# Top.net
KiCad netlist of a schematic drawn in Altium Designer
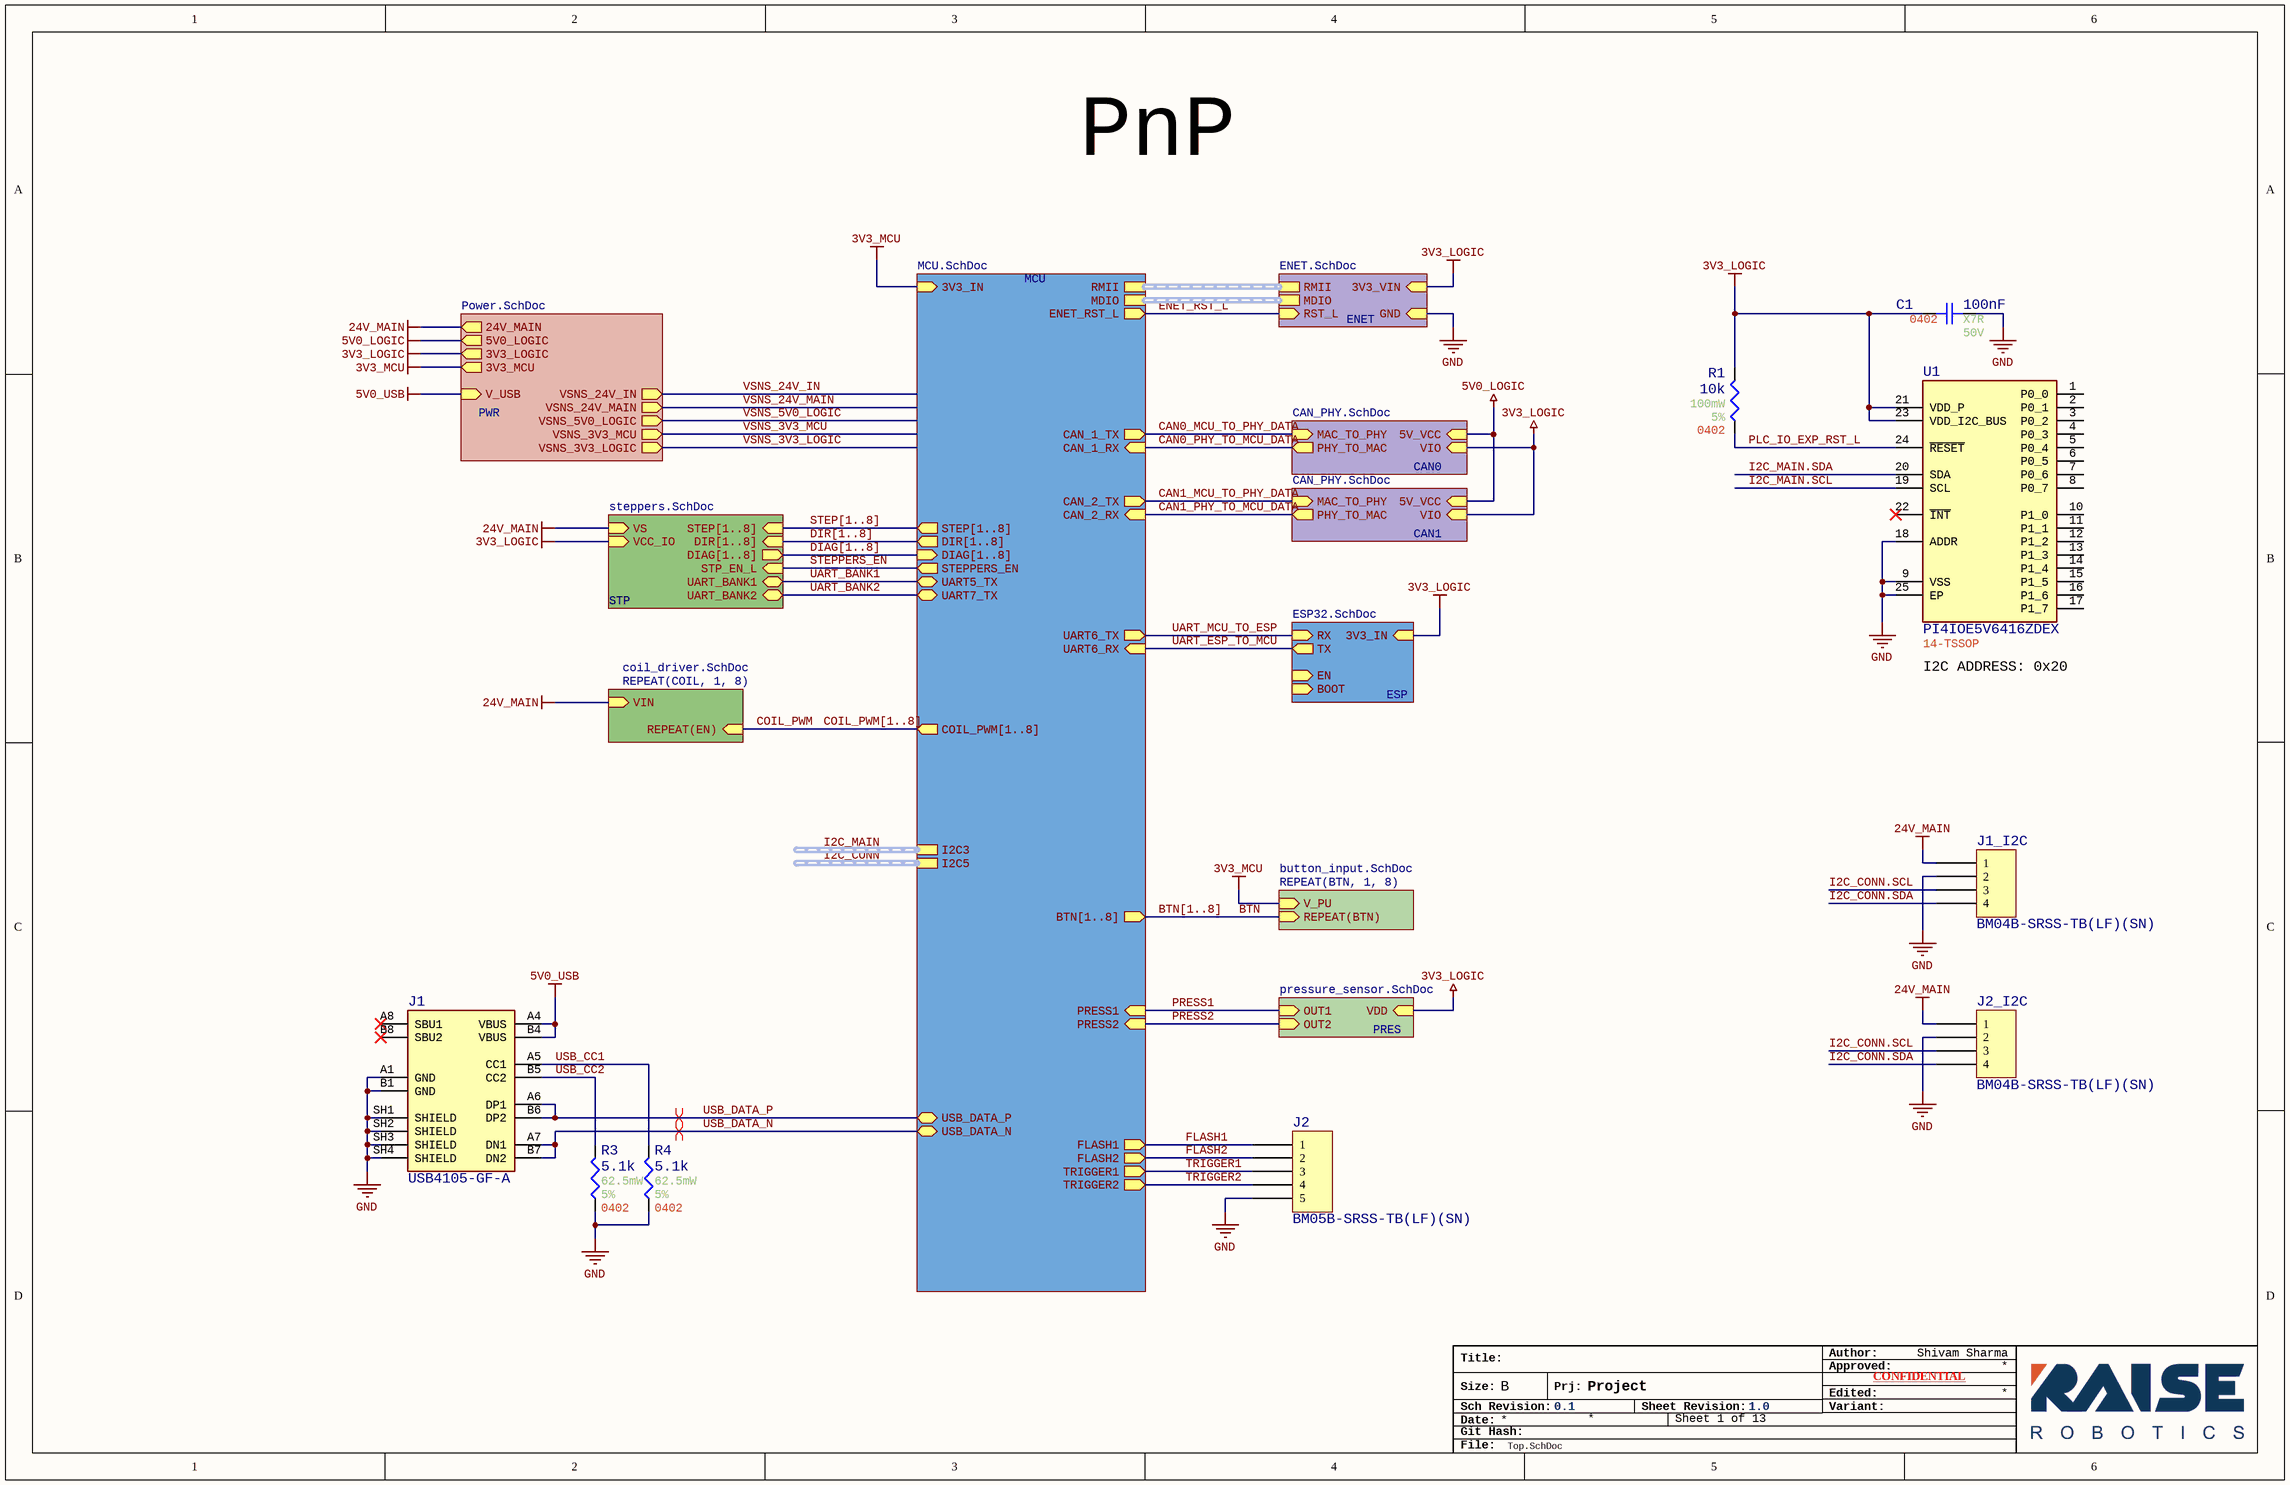
[diagram p0: Top.SchDoc]

(export (version "E")
  (design (tool "Eeschema 10.0.6"))
  (components
    (comp (ref "C1")
      (value "100nF")
      (footprint "Generic 0402 capacitor")
      (fields
        (field (name "TEMPERATURE COEFFICIENT") "X7R")
        (field (name "VOLTAGE RATING") "50V")
        (field (name "CASE/PACKAGE") "0402")
        (field (name "TOLERANCE") "10%")
        (field (name "Comment") "GRT155R71H104KE01D")
      )
      (libsource (lib "Raise Robotics") (part "Unpolarized Capacitor"))
    )
    (comp (ref "J1")
      (value "USB4105-GF-A")
      (footprint "USB-C_USB4105-GF-A")
      (description "USB Connector, 24 Contact(s), Female, Right Angle, Solder Terminal, Locking, Receptacle")
      (fields (field (name "MANUFACTURER") "Molex"))
      (libsource (lib "Raise Robotics") (part "USB4105-GF-A"))
    )
    (comp (ref "J1_I2C")
      (value "BM04B-SRSS-TB(LF)(SN)")
      (footprint "JST BM04B-SRSS-TB")
      (description "CONN HEADER SMD 4POS 1MM")
      (fields (field (name "MANUFACTURER") "JST Sales America Inc."))
      (libsource (lib "Celestial Altium Library - altium_library") (part "4 Pin"))
    )
    (comp (ref "J2")
      (value "BM05B-SRSS-TB(LF)(SN)")
      (footprint "JST BM05B-SRSS-TB")
      (description "CONN HEADER SMD 5POS 1MM")
      (fields (field (name "MANUFACTURER") "JST Sales America Inc."))
      (libsource (lib "Celestial Altium Library - altium_library") (part "5 Pin"))
    )
    (comp (ref "J2_I2C")
      (value "BM04B-SRSS-TB(LF)(SN)")
      (footprint "JST BM04B-SRSS-TB")
      (description "CONN HEADER SMD 4POS 1MM")
      (fields (field (name "MANUFACTURER") "JST Sales America Inc."))
      (libsource (lib "Celestial Altium Library - altium_library") (part "4 Pin"))
    )
    (comp (ref "R1")
      (value "10k")
      (footprint "Generic 0402 Resistor")
      (description "Res Thick Film 0402 10K Ohm 5% 1/10W ±200ppm/°C Molded SMD Punched Carrier T/R")
      (fields
        (field (name "POWER") "100mW")
        (field (name "TOLERANCE") "5%")
        (field (name "CASE/PACKAGE") "0402")
        (field (name "Comment") "ERJ-2GEJ103X")
      )
      (libsource (lib "Raise Robotics") (part "Resistor"))
    )
    (comp (ref "R3")
      (value "5.1k")
      (footprint "Generic 0402 Resistor")
      (description "Res Thick Film 0402 5.1K Ohm 5% 0.063W ±100ppm/°C Molded SMD Paper T/R")
      (fields
        (field (name "POWER") "62.5mW")
        (field (name "TOLERANCE") "5%")
        (field (name "CASE/PACKAGE") "0402")
        (field (name "Comment") "RMCF0402JT5K10")
      )
      (libsource (lib "Raise Robotics") (part "Resistor"))
    )
    (comp (ref "R4")
      (value "5.1k")
      (footprint "Generic 0402 Resistor")
      (description "Res Thick Film 0402 5.1K Ohm 5% 0.063W ±100ppm/°C Molded SMD Paper T/R")
      (fields
        (field (name "POWER") "62.5mW")
        (field (name "TOLERANCE") "5%")
        (field (name "CASE/PACKAGE") "0402")
        (field (name "Comment") "RMCF0402JT5K10")
      )
      (libsource (lib "Raise Robotics") (part "Resistor"))
    )
    (comp (ref "U1")
      (value "PI4IOE5V6416ZDEX")
      (footprint "PI4IOE5V6416ZDEX")
      (description "16-bit I2C General Purpose IO Expander with Interrupt, Reset, -40 to 85 °C, RoHS")
      (fields (field (name "CASE/PACKAGE") "14-TSSOP"))
      (libsource (lib "Raise Robotics") (part "PI4IOE5V6416ZDEX"))
    )
  )
  (nets
    (net (code "56") (name "/FLASH1") (class "Default")
      (node (ref "J2") (pin "1") (pinfunction "1_1") (pintype "passive"))
    )
    (net (code "57") (name "/FLASH2") (class "Default")
      (node (ref "J2") (pin "2") (pinfunction "2_2") (pintype "passive"))
    )
    (net (code "58") (name "/I2C_CONN.SCL") (class "Default")
      (node (ref "J1_I2C") (pin "3") (pinfunction "3_3") (pintype "passive"))
      (node (ref "J2_I2C") (pin "3") (pinfunction "3_3") (pintype "passive"))
    )
    (net (code "59") (name "/I2C_CONN.SDA") (class "Default")
      (node (ref "J1_I2C") (pin "4") (pinfunction "4_4") (pintype "passive"))
      (node (ref "J2_I2C") (pin "4") (pinfunction "4_4") (pintype "passive"))
    )
    (net (code "60") (name "/I2C_MAIN.SCL") (class "Default")
      (node (ref "U1") (pin "19") (pinfunction "SCL_19") (pintype "passive"))
    )
    (net (code "61") (name "/I2C_MAIN.SDA") (class "Default")
      (node (ref "U1") (pin "20") (pinfunction "SDA_20") (pintype "passive"))
    )
    (net (code "63") (name "/PLC_IO_EXP_RST_L") (class "Default")
      (node (ref "R1") (pin "1") (pinfunction "1_1") (pintype "passive"))
      (node (ref "U1") (pin "24") (pinfunction "~{RESET}_24") (pintype "passive"))
    )
    (net (code "69") (name "/TRIGGER1") (class "Default")
      (node (ref "J2") (pin "3") (pinfunction "3_3") (pintype "passive"))
    )
    (net (code "70") (name "/TRIGGER2") (class "Default")
      (node (ref "J2") (pin "4") (pinfunction "4_4") (pintype "passive"))
    )
    (net (code "75") (name "/USB_CC1") (class "Default")
      (node (ref "J1") (pin "A5") (pinfunction "CC1_A5") (pintype "passive"))
      (node (ref "R4") (pin "2") (pinfunction "2_2") (pintype "passive"))
    )
    (net (code "76") (name "/USB_CC2") (class "Default")
      (node (ref "J1") (pin "B5") (pinfunction "CC2_B5") (pintype "passive"))
      (node (ref "R3") (pin "2") (pinfunction "2_2") (pintype "passive"))
    )
    (net (code "77") (name "/USB_DATA_N") (class "Default")
      (node (ref "J1") (pin "A7") (pinfunction "DN1_A7") (pintype "passive"))
      (node (ref "J1") (pin "B7") (pinfunction "DN2_B7") (pintype "passive"))
    )
    (net (code "78") (name "/USB_DATA_P") (class "Default")
      (node (ref "J1") (pin "A6") (pinfunction "DP1_A6") (pintype "passive"))
      (node (ref "J1") (pin "B6") (pinfunction "DP2_B6") (pintype "passive"))
    )
    (net (code "86") (name "3V3_LOGIC") (class "Default")
      (node (ref "C1") (pin "2") (pinfunction "2_2") (pintype "passive"))
      (node (ref "R1") (pin "2") (pinfunction "2_2") (pintype "passive"))
      (node (ref "U1") (pin "21") (pinfunction "VDD_P_21") (pintype "passive"))
      (node (ref "U1") (pin "23") (pinfunction "VDD_I2C_BUS_23") (pintype "passive"))
    )
    (net (code "89") (name "5V0_USB") (class "Default")
      (node (ref "J1") (pin "A4") (pinfunction "VBUS_A4") (pintype "passive"))
      (node (ref "J1") (pin "B4") (pinfunction "VBUS_B4") (pintype "passive"))
    )
    (net (code "90") (name "24V_MAIN") (class "Default")
      (node (ref "J1_I2C") (pin "1") (pinfunction "1_1") (pintype "passive"))
      (node (ref "J2_I2C") (pin "1") (pinfunction "1_1") (pintype "passive"))
    )
    (net (code "91") (name "GND") (class "Default")
      (node (ref "C1") (pin "1") (pinfunction "1_1") (pintype "passive"))
      (node (ref "J1") (pin "A1") (pinfunction "GND_A1") (pintype "passive"))
      (node (ref "J1") (pin "B1") (pinfunction "GND_B1") (pintype "passive"))
      (node (ref "J1") (pin "SH1") (pinfunction "SHIELD_SH1") (pintype "passive"))
      (node (ref "J1") (pin "SH2") (pinfunction "SHIELD_SH2") (pintype "passive"))
      (node (ref "J1") (pin "SH3") (pinfunction "SHIELD_SH3") (pintype "passive"))
      (node (ref "J1") (pin "SH4") (pinfunction "SHIELD_SH4") (pintype "passive"))
      (node (ref "J1_I2C") (pin "2") (pinfunction "2_2") (pintype "passive"))
      (node (ref "J2") (pin "5") (pinfunction "5_5") (pintype "passive"))
      (node (ref "J2_I2C") (pin "2") (pinfunction "2_2") (pintype "passive"))
      (node (ref "R3") (pin "1") (pinfunction "1_1") (pintype "passive"))
      (node (ref "R4") (pin "1") (pinfunction "1_1") (pintype "passive"))
      (node (ref "U1") (pin "18") (pinfunction "ADDR_18") (pintype "passive"))
      (node (ref "U1") (pin "25") (pinfunction "EP_25") (pintype "passive"))
      (node (ref "U1") (pin "9") (pinfunction "VSS_9") (pintype "passive"))
    )
    (net (code "92") (name "unconnected-(J1-SBU1-PadA8)") (class "Default")
      (node (ref "J1") (pin "A8") (pinfunction "SBU1_A8") (pintype "passive+no_connect"))
    )
    (net (code "93") (name "unconnected-(J1-SBU2-PadB8)") (class "Default")
      (node (ref "J1") (pin "B8") (pinfunction "SBU2_B8") (pintype "passive+no_connect"))
    )
    (net (code "94") (name "unconnected-(U1-P0_0-Pad1)") (class "Default")
      (node (ref "U1") (pin "1") (pinfunction "P0_0_1") (pintype "passive"))
    )
    (net (code "95") (name "unconnected-(U1-P0_1-Pad2)") (class "Default")
      (node (ref "U1") (pin "2") (pinfunction "P0_1_2") (pintype "passive"))
    )
    (net (code "96") (name "unconnected-(U1-P0_2-Pad3)") (class "Default")
      (node (ref "U1") (pin "3") (pinfunction "P0_2_3") (pintype "passive"))
    )
    (net (code "97") (name "unconnected-(U1-P0_3-Pad4)") (class "Default")
      (node (ref "U1") (pin "4") (pinfunction "P0_3_4") (pintype "passive"))
    )
    (net (code "98") (name "unconnected-(U1-P0_4-Pad5)") (class "Default")
      (node (ref "U1") (pin "5") (pinfunction "P0_4_5") (pintype "passive"))
    )
    (net (code "99") (name "unconnected-(U1-P0_5-Pad6)") (class "Default")
      (node (ref "U1") (pin "6") (pinfunction "P0_5_6") (pintype "passive"))
    )
    (net (code "100") (name "unconnected-(U1-P0_6-Pad7)") (class "Default")
      (node (ref "U1") (pin "7") (pinfunction "P0_6_7") (pintype "passive"))
    )
    (net (code "101") (name "unconnected-(U1-P0_7-Pad8)") (class "Default")
      (node (ref "U1") (pin "8") (pinfunction "P0_7_8") (pintype "passive"))
    )
    (net (code "102") (name "unconnected-(U1-P1_0-Pad10)") (class "Default")
      (node (ref "U1") (pin "10") (pinfunction "P1_0_10") (pintype "passive"))
    )
    (net (code "103") (name "unconnected-(U1-P1_1-Pad11)") (class "Default")
      (node (ref "U1") (pin "11") (pinfunction "P1_1_11") (pintype "passive"))
    )
    (net (code "104") (name "unconnected-(U1-P1_2-Pad12)") (class "Default")
      (node (ref "U1") (pin "12") (pinfunction "P1_2_12") (pintype "passive"))
    )
    (net (code "105") (name "unconnected-(U1-P1_3-Pad13)") (class "Default")
      (node (ref "U1") (pin "13") (pinfunction "P1_3_13") (pintype "passive"))
    )
    (net (code "106") (name "unconnected-(U1-P1_4-Pad14)") (class "Default")
      (node (ref "U1") (pin "14") (pinfunction "P1_4_14") (pintype "passive"))
    )
    (net (code "107") (name "unconnected-(U1-P1_5-Pad15)") (class "Default")
      (node (ref "U1") (pin "15") (pinfunction "P1_5_15") (pintype "passive"))
    )
    (net (code "108") (name "unconnected-(U1-P1_6-Pad16)") (class "Default")
      (node (ref "U1") (pin "16") (pinfunction "P1_6_16") (pintype "passive"))
    )
    (net (code "109") (name "unconnected-(U1-P1_7-Pad17)") (class "Default")
      (node (ref "U1") (pin "17") (pinfunction "P1_7_17") (pintype "passive"))
    )
    (net (code "110") (name "unconnected-(U1-~{INT}-Pad22)") (class "Default")
      (node (ref "U1") (pin "22") (pinfunction "~{INT}_22") (pintype "passive+no_connect"))
    )
  )
)
